# SCH_popup_2025-01-21.net
KiCad netlist of a schematic drawn in EasyEDA
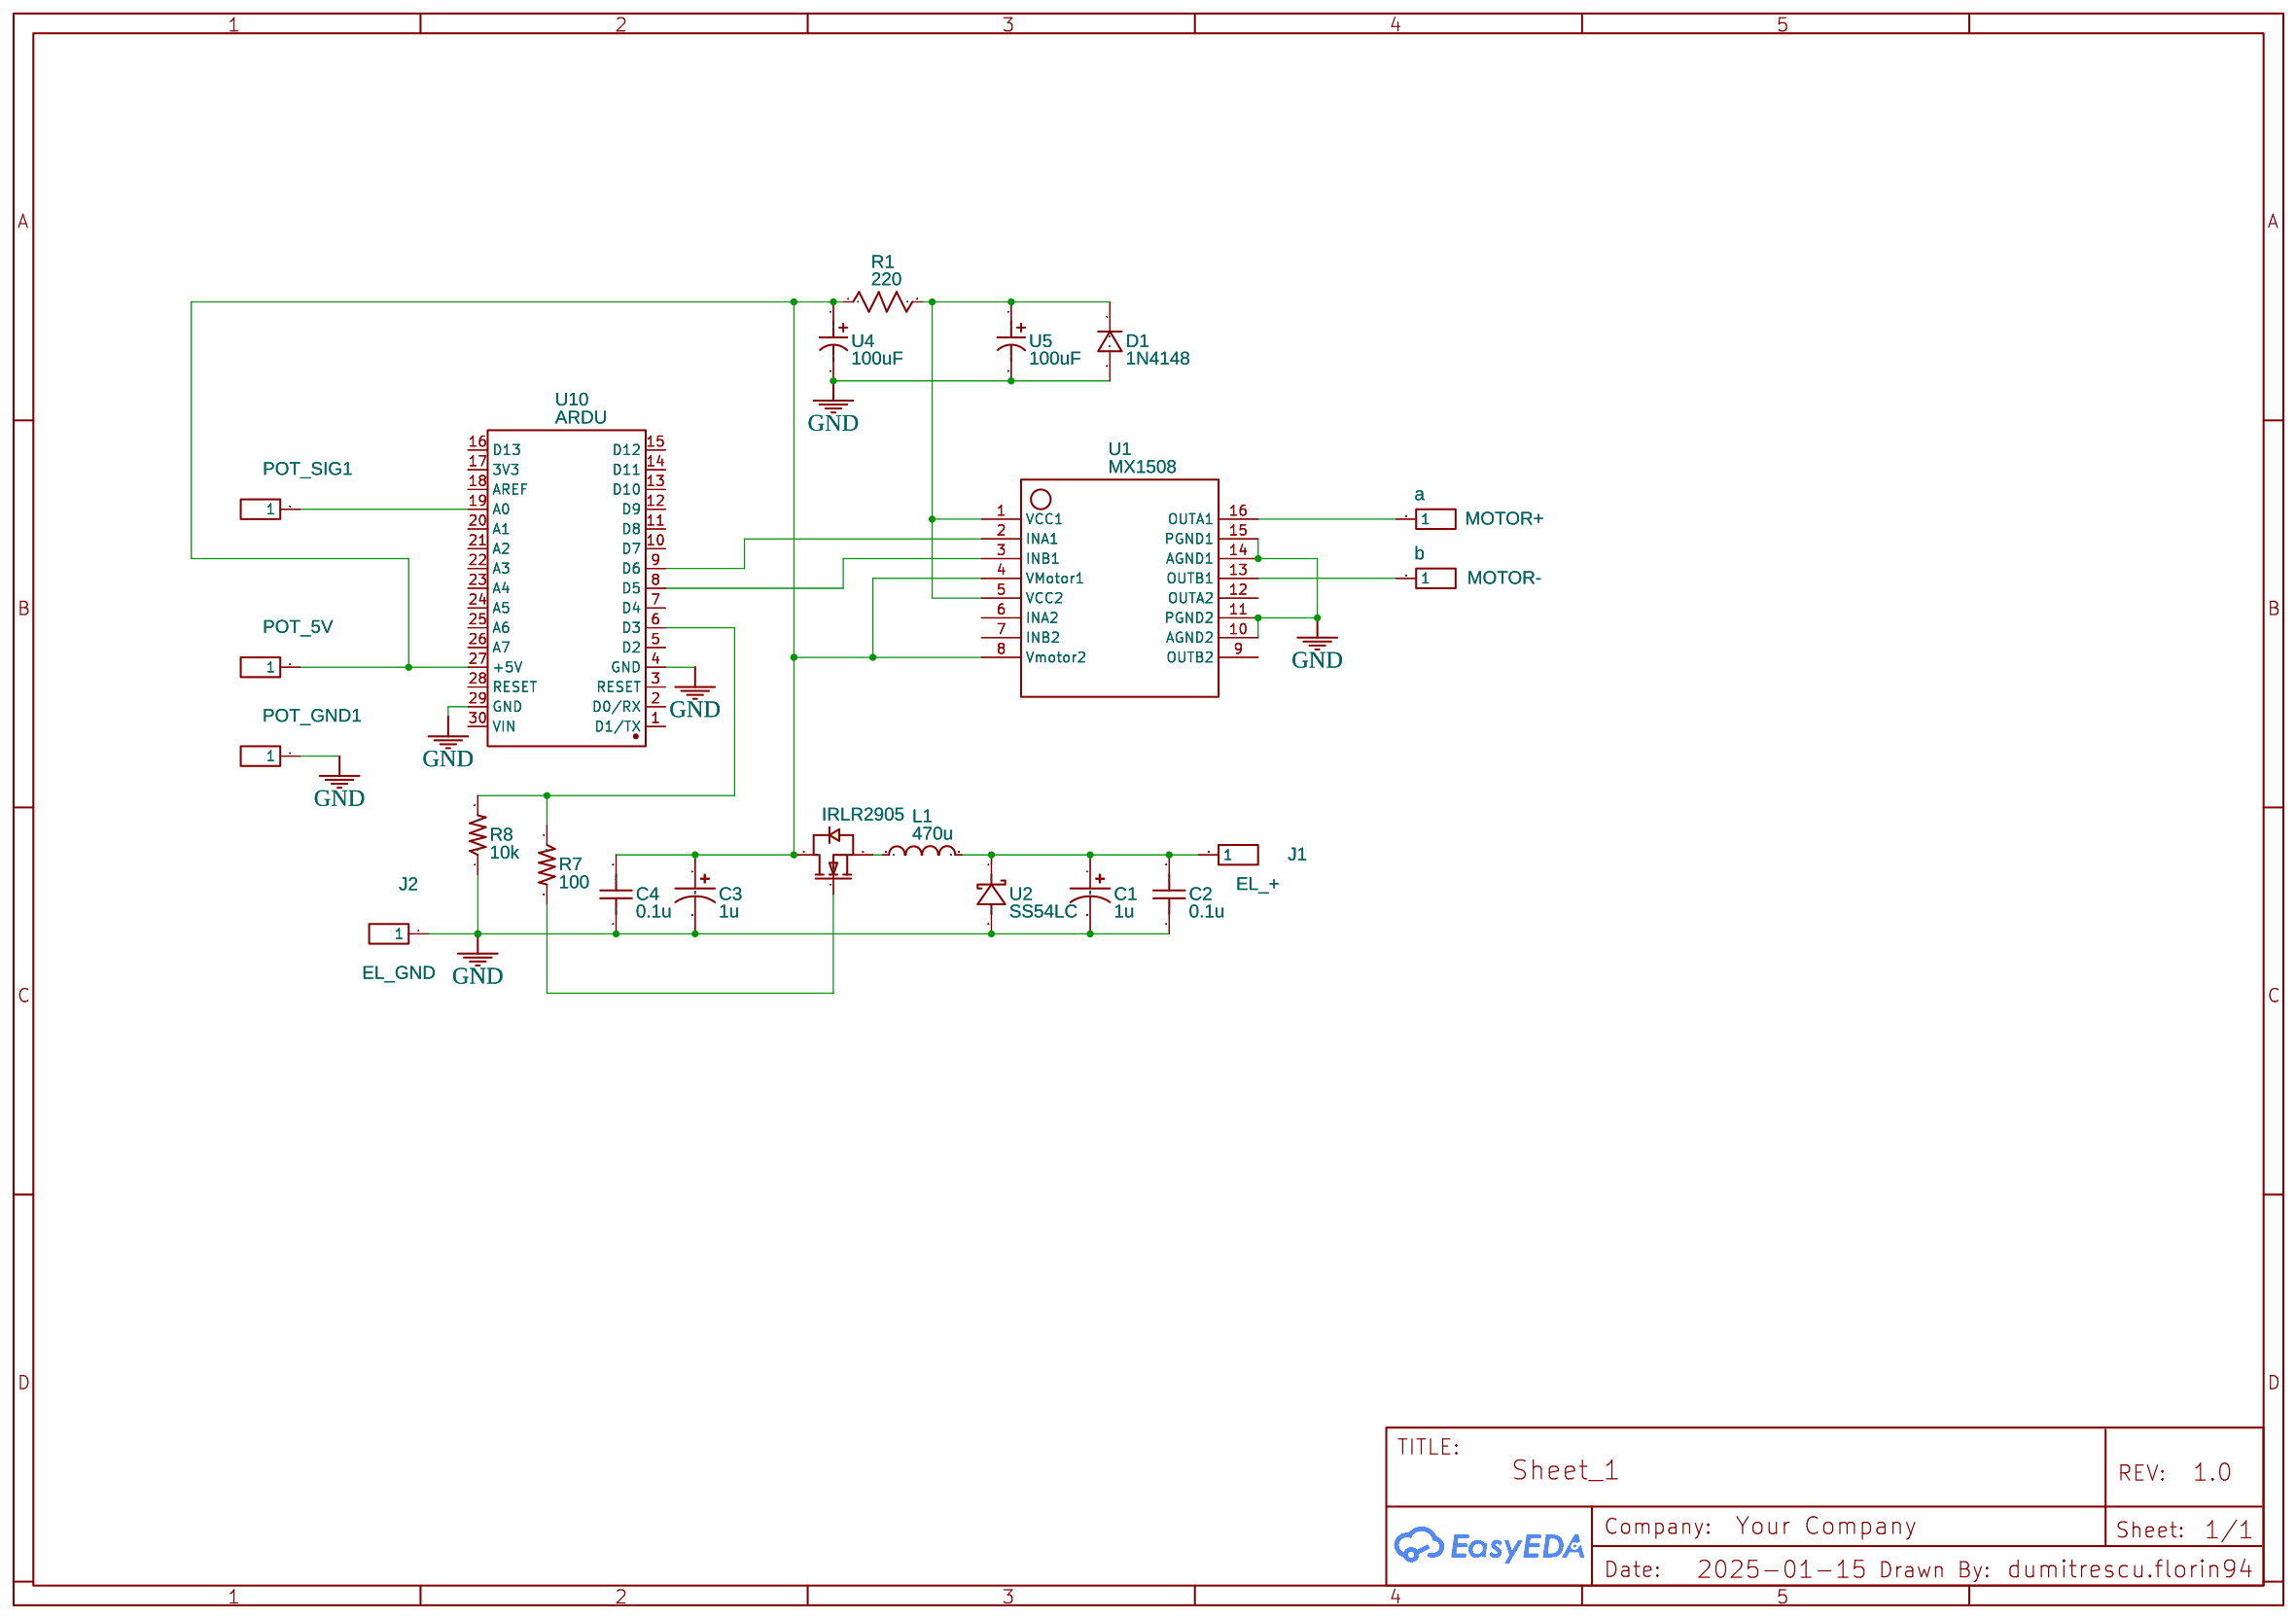
[diagram p0: schematic sheet]

(export (version "E")
  (design (tool "Eeschema 10.0.6"))
  (components
    (comp (ref "C1") (value "1u") (libsource (lib "") (part "CE_TH_D6.3×F2.5_US")))
    (comp (ref "C2") (value "0.1u") (libsource (lib "") (part "C_0805_US")))
    (comp (ref "C3") (value "1u") (libsource (lib "") (part "CE_TH_D10.0×F5.0_US")))
    (comp (ref "C4") (value "0.1u") (libsource (lib "") (part "C_0805_US")))
    (comp (ref "D1")
      (value "1N4148")
      (fields (field (name "Manufacturer") "STMicroelectronics"))
      (libsource (lib "") (part "1N4148"))
    )
    (comp (ref "J1") (value "EL_+") (libsource (lib "") (part "HDR-M-2.54_1x1_2")))
    (comp (ref "J2") (value "EL_GND") (libsource (lib "") (part "HDR-M-2.54_1x1_3")))
    (comp (ref "L1") (value "470u") (libsource (lib "") (part "L_AXIAL-0.6_US")))
    (comp (ref "MOTOR+") (value "a") (libsource (lib "") (part "HDR-M-2.54_1x1_4")))
    (comp (ref "MOTOR-") (value "b") (libsource (lib "") (part "HDR-M-2.54_1x1")))
    (comp (ref "POT_5V") (value "MINUS") (libsource (lib "") (part "HDR-M-2.54_1x1_6")))
    (comp (ref "POT_GND1") (value "MINUS") (libsource (lib "") (part "HDR-M-2.54_1x1_5")))
    (comp (ref "POT_SIG1") (value "MINUS") (libsource (lib "") (part "HDR-M-2.54_1x1_1")))
    (comp (ref "R1") (value "220") (libsource (lib "") (part "R_0201_US")))
    (comp (ref "R7") (value "100") (libsource (lib "") (part "RESISTORPTH-16W_1")))
    (comp (ref "R8") (value "10k") (libsource (lib "") (part "RESISTORPTH-16W")))
    (comp (ref "U1") (value "MX1508") (libsource (lib "") (part "MX1508")))
    (comp (ref "U2")
      (value "SS54LC")
      (fields (field (name "Manufacturer") "JUXING(钜兴)"))
      (libsource (lib "") (part "SS54LC"))
    )
    (comp (ref "U4")
      (value "100uF")
      (fields
        (field (name "Manufacturer Part") "RX100UF35V90RV0103")
        (field (name "Manufacturer") "KNSCHA(科尼盛)")
      )
      (libsource (lib "") (part "RX100UF35V90RV0103"))
    )
    (comp (ref "U5")
      (value "100uF")
      (fields
        (field (name "Manufacturer Part") "RX100UF35V90RV0103")
        (field (name "Manufacturer") "KNSCHA(科尼盛)")
      )
      (libsource (lib "") (part "RX100UF35V90RV0103"))
    )
    (comp (ref "U7")
      (value "IRLR2905")
      (fields (field (name "Manufacturer") "TECH PUBLIC(台舟)"))
      (libsource (lib "") (part "IRLR2905"))
    )
    (comp (ref "U10")
      (value "ARDU")
      (fields (field (name "Manufacturer Part") "ARDUINO_NANO"))
      (libsource (lib "") (part "ARDUINO_NANO"))
    )
  )
  (nets
    (net (code "1") (name "GND") (class "Default")
      (node (ref "C1") (pin "2") (pinfunction "2_2") (pintype "unspecified"))
      (node (ref "C2") (pin "1") (pinfunction "1_1") (pintype "unspecified"))
      (node (ref "C3") (pin "2") (pinfunction "2_2") (pintype "unspecified"))
      (node (ref "C4") (pin "1") (pinfunction "1_1") (pintype "unspecified"))
      (node (ref "D1") (pin "2") (pinfunction "2_2") (pintype "unspecified"))
      (node (ref "J2") (pin "1") (pinfunction "1_1") (pintype "input"))
      (node (ref "POT_GND1") (pin "1") (pinfunction "1_1") (pintype "input"))
      (node (ref "R8") (pin "1") (pinfunction "1_1") (pintype "unspecified"))
      (node (ref "U1") (pin "10") (pinfunction "AGND2_10") (pintype "unspecified"))
      (node (ref "U1") (pin "11") (pinfunction "PGND2_11") (pintype "unspecified"))
      (node (ref "U1") (pin "14") (pinfunction "AGND1_14") (pintype "unspecified"))
      (node (ref "U1") (pin "15") (pinfunction "PGND1_15") (pintype "unspecified"))
      (node (ref "U10") (pin "29") (pinfunction "GND_29") (pintype "unspecified"))
      (node (ref "U10") (pin "4") (pinfunction "GND_4") (pintype "unspecified"))
      (node (ref "U2") (pin "2") (pinfunction "A_2") (pintype "unspecified"))
      (node (ref "U4") (pin "2") (pinfunction "2_2") (pintype "input"))
      (node (ref "U5") (pin "2") (pinfunction "2_2") (pintype "input"))
    )
    (net (code "2") (name "Net-(U1-INA1)") (class "Default")
      (node (ref "U1") (pin "2") (pinfunction "INA1_2") (pintype "unspecified"))
      (node (ref "U10") (pin "9") (pinfunction "D6_9") (pintype "unspecified"))
    )
    (net (code "3") (name "Net-(U1-INB1)") (class "Default")
      (node (ref "U1") (pin "3") (pinfunction "INB1_3") (pintype "unspecified"))
      (node (ref "U10") (pin "8") (pinfunction "D5_8") (pintype "unspecified"))
    )
    (net (code "4") (name "Net-(U1-OUTA1)") (class "Default")
      (node (ref "MOTOR+") (pin "1") (pinfunction "1_1") (pintype "input"))
      (node (ref "U1") (pin "16") (pinfunction "OUTA1_16") (pintype "unspecified"))
    )
    (net (code "5") (name "Net-(U1-OUTB1)") (class "Default")
      (node (ref "MOTOR-") (pin "1") (pinfunction "1_1") (pintype "input"))
      (node (ref "U1") (pin "13") (pinfunction "OUTB1_13") (pintype "unspecified"))
    )
    (net (code "6") (name "Net-(U1-VCC1)") (class "Default")
      (node (ref "D1") (pin "1") (pinfunction "1_1") (pintype "unspecified"))
      (node (ref "R1") (pin "2") (pinfunction "2_2") (pintype "unspecified"))
      (node (ref "U1") (pin "1") (pinfunction "VCC1_1") (pintype "unspecified"))
      (node (ref "U1") (pin "5") (pinfunction "VCC2_5") (pintype "unspecified"))
      (node (ref "U5") (pin "1") (pinfunction "1_1") (pintype "input"))
    )
    (net (code "7") (name "Net-(U1-VMotor1)") (class "Default")
      (node (ref "C3") (pin "1") (pinfunction "1_1") (pintype "unspecified"))
      (node (ref "C4") (pin "2") (pinfunction "2_2") (pintype "unspecified"))
      (node (ref "POT_5V") (pin "1") (pinfunction "1_1") (pintype "input"))
      (node (ref "R1") (pin "1") (pinfunction "1_1") (pintype "unspecified"))
      (node (ref "U1") (pin "4") (pinfunction "VMotor1_4") (pintype "unspecified"))
      (node (ref "U1") (pin "8") (pinfunction "Vmotor2_8") (pintype "unspecified"))
      (node (ref "U10") (pin "27") (pinfunction "+5V_27") (pintype "unspecified"))
      (node (ref "U4") (pin "1") (pinfunction "1_1") (pintype "input"))
      (node (ref "U7") (pin "2") (pinfunction "D_2") (pintype "unspecified"))
    )
    (net (code "8") (name "Net-(U2-K)") (class "Default")
      (node (ref "C1") (pin "1") (pinfunction "1_1") (pintype "unspecified"))
      (node (ref "C2") (pin "2") (pinfunction "2_2") (pintype "unspecified"))
      (node (ref "J1") (pin "1") (pinfunction "1_1") (pintype "input"))
      (node (ref "L1") (pin "2") (pinfunction "2_2") (pintype "unspecified"))
      (node (ref "U2") (pin "1") (pinfunction "K_1") (pintype "unspecified"))
    )
    (net (code "9") (name "Net-(U7-G)") (class "Default")
      (node (ref "R7") (pin "2") (pinfunction "2_2") (pintype "unspecified"))
      (node (ref "U7") (pin "1") (pinfunction "G_1") (pintype "unspecified"))
    )
    (net (code "10") (name "Net-(U7-S)") (class "Default")
      (node (ref "L1") (pin "1") (pinfunction "1_1") (pintype "unspecified"))
      (node (ref "U7") (pin "3") (pinfunction "S_3") (pintype "unspecified"))
    )
    (net (code "11") (name "Net-(U10-A0)") (class "Default")
      (node (ref "POT_SIG1") (pin "1") (pinfunction "1_1") (pintype "input"))
      (node (ref "U10") (pin "19") (pinfunction "A0_19") (pintype "unspecified"))
    )
    (net (code "12") (name "Net-(U10-D3)") (class "Default")
      (node (ref "R7") (pin "1") (pinfunction "1_1") (pintype "unspecified"))
      (node (ref "R8") (pin "2") (pinfunction "2_2") (pintype "unspecified"))
      (node (ref "U10") (pin "6") (pinfunction "D3_6") (pintype "unspecified"))
    )
    (net (code "13") (name "unconnected-(U1-INA2-Pad6)") (class "Default")
      (node (ref "U1") (pin "6") (pinfunction "INA2_6") (pintype "unspecified"))
    )
    (net (code "14") (name "unconnected-(U1-INB2-Pad7)") (class "Default")
      (node (ref "U1") (pin "7") (pinfunction "INB2_7") (pintype "unspecified"))
    )
    (net (code "15") (name "unconnected-(U1-OUTA2-Pad12)") (class "Default")
      (node (ref "U1") (pin "12") (pinfunction "OUTA2_12") (pintype "unspecified"))
    )
    (net (code "16") (name "unconnected-(U1-OUTB2-Pad9)") (class "Default")
      (node (ref "U1") (pin "9") (pinfunction "OUTB2_9") (pintype "unspecified"))
    )
    (net (code "17") (name "unconnected-(U10-3V3-Pad17)") (class "Default")
      (node (ref "U10") (pin "17") (pinfunction "3V3_17") (pintype "unspecified"))
    )
    (net (code "18") (name "unconnected-(U10-A1-Pad20)") (class "Default")
      (node (ref "U10") (pin "20") (pinfunction "A1_20") (pintype "unspecified"))
    )
    (net (code "19") (name "unconnected-(U10-A2-Pad21)") (class "Default")
      (node (ref "U10") (pin "21") (pinfunction "A2_21") (pintype "unspecified"))
    )
    (net (code "20") (name "unconnected-(U10-A3-Pad22)") (class "Default")
      (node (ref "U10") (pin "22") (pinfunction "A3_22") (pintype "unspecified"))
    )
    (net (code "21") (name "unconnected-(U10-A4-Pad23)") (class "Default")
      (node (ref "U10") (pin "23") (pinfunction "A4_23") (pintype "unspecified"))
    )
    (net (code "22") (name "unconnected-(U10-A5-Pad24)") (class "Default")
      (node (ref "U10") (pin "24") (pinfunction "A5_24") (pintype "unspecified"))
    )
    (net (code "23") (name "unconnected-(U10-A6-Pad25)") (class "Default")
      (node (ref "U10") (pin "25") (pinfunction "A6_25") (pintype "unspecified"))
    )
    (net (code "24") (name "unconnected-(U10-A7-Pad26)") (class "Default")
      (node (ref "U10") (pin "26") (pinfunction "A7_26") (pintype "unspecified"))
    )
    (net (code "25") (name "unconnected-(U10-AREF-Pad18)") (class "Default")
      (node (ref "U10") (pin "18") (pinfunction "AREF_18") (pintype "unspecified"))
    )
    (net (code "26") (name "unconnected-(U10-D0{slash}RX-Pad2)") (class "Default")
      (node (ref "U10") (pin "2") (pinfunction "D0/RX_2") (pintype "unspecified"))
    )
    (net (code "27") (name "unconnected-(U10-D1{slash}TX-Pad1)") (class "Default")
      (node (ref "U10") (pin "1") (pinfunction "D1/TX_1") (pintype "unspecified"))
    )
    (net (code "28") (name "unconnected-(U10-D2-Pad5)") (class "Default")
      (node (ref "U10") (pin "5") (pinfunction "D2_5") (pintype "unspecified"))
    )
    (net (code "29") (name "unconnected-(U10-D4-Pad7)") (class "Default")
      (node (ref "U10") (pin "7") (pinfunction "D4_7") (pintype "unspecified"))
    )
    (net (code "30") (name "unconnected-(U10-D7-Pad10)") (class "Default")
      (node (ref "U10") (pin "10") (pinfunction "D7_10") (pintype "unspecified"))
    )
    (net (code "31") (name "unconnected-(U10-D8-Pad11)") (class "Default")
      (node (ref "U10") (pin "11") (pinfunction "D8_11") (pintype "unspecified"))
    )
    (net (code "32") (name "unconnected-(U10-D9-Pad12)") (class "Default")
      (node (ref "U10") (pin "12") (pinfunction "D9_12") (pintype "unspecified"))
    )
    (net (code "33") (name "unconnected-(U10-D10-Pad13)") (class "Default")
      (node (ref "U10") (pin "13") (pinfunction "D10_13") (pintype "unspecified"))
    )
    (net (code "34") (name "unconnected-(U10-D11-Pad14)") (class "Default")
      (node (ref "U10") (pin "14") (pinfunction "D11_14") (pintype "unspecified"))
    )
    (net (code "35") (name "unconnected-(U10-D12-Pad15)") (class "Default")
      (node (ref "U10") (pin "15") (pinfunction "D12_15") (pintype "unspecified"))
    )
    (net (code "36") (name "unconnected-(U10-D13-Pad16)") (class "Default")
      (node (ref "U10") (pin "16") (pinfunction "D13_16") (pintype "unspecified"))
    )
    (net (code "37") (name "unconnected-(U10-RESET-Pad3)") (class "Default")
      (node (ref "U10") (pin "3") (pinfunction "RESET_3") (pintype "unspecified"))
    )
    (net (code "38") (name "unconnected-(U10-RESET-Pad28)") (class "Default")
      (node (ref "U10") (pin "28") (pinfunction "RESET_28") (pintype "unspecified"))
    )
    (net (code "39") (name "unconnected-(U10-VIN-Pad30)") (class "Default")
      (node (ref "U10") (pin "30") (pinfunction "VIN_30") (pintype "unspecified"))
    )
  )
)
